# Balance_V0_1.net
KiCad netlist of a schematic drawn in Altium Designer
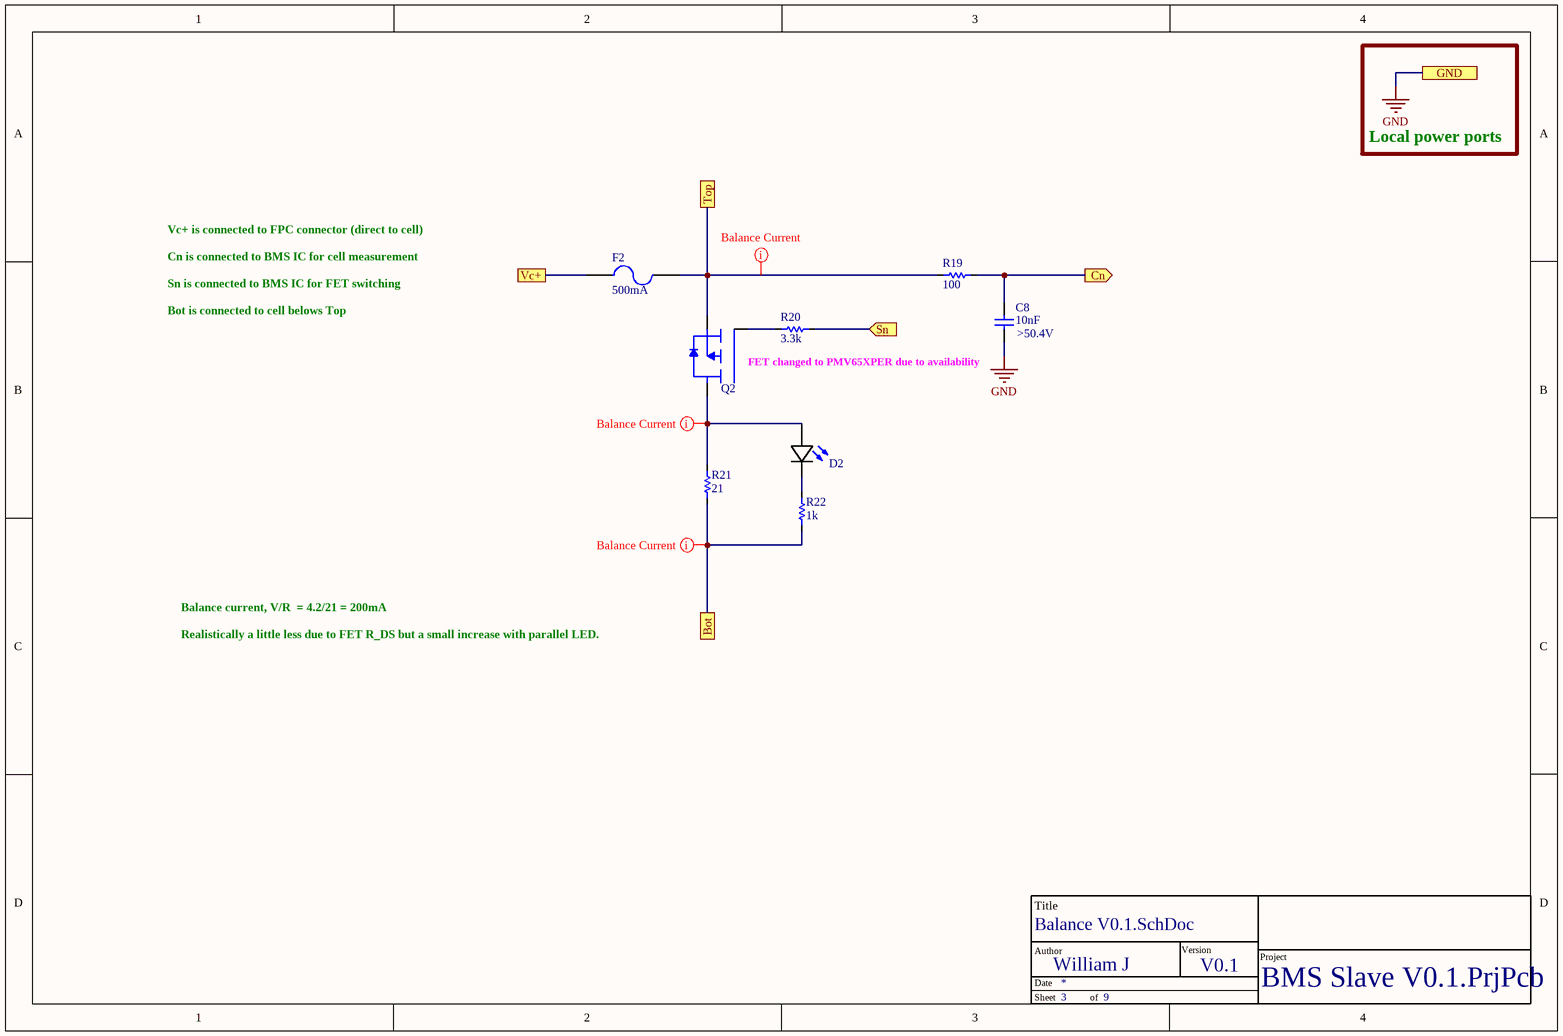
[diagram p0: Balance V0.1.SchDoc]

(export (version "E")
  (design (tool "Eeschema 10.0.6"))
  (components
    (comp (ref "*") (value "TitleBlock") (libsource (lib "SchematicLib") (part "TitleBlock")))
    (comp (ref "C8")
      (value "10nF")
      (footprint "C_0402")
      (description "Capacitor")
      (fields (field (name "VOLTAGE") ">50.4V") (field (name "Comment") "C1005X7S2A103K050BB"))
      (libsource (lib "Passives") (part "Capacitor"))
    )
    (comp (ref "D2")
      (value "150060BS55040")
      (footprint "LED (0603)")
      (description "LED BLUE DIFFUSED 0603 SMD")
      (fields (field (name "MANUFACTURER") "Wurth Electronics"))
      (libsource (lib "LEDLib") (part "150060BS55040"))
    )
    (comp (ref "F2")
      (value "0466.500NR")
      (footprint "0466.500NR")
      (fields
        (field (name "MANUFACTURER") "Littelfuse")
        (field (name "CURRENT RATING") "500mA")
        (field (name "PUBLISHER") "Altium Limited")
      )
      (libsource (lib "Miscellaneous Devices") (part "Fuse 2"))
    )
    (comp (ref "Q2")
      (value "NX2301PVL")
      (footprint "SOT95P230X110-3N")
      (description "MOSFET 20V P-Channel 2A")
      (libsource (lib "SchematicLib") (part "NX2301PVL"))
    )
    (comp (ref "R19")
      (value "100")
      (footprint "R_0402")
      (description "Resistor")
      (fields (field (name "Comment") "RC0402FR-07100RL"))
      (libsource (lib "Passives") (part "Resistor"))
    )
    (comp (ref "R20")
      (value "3.3k")
      (footprint "R_0402")
      (description "Resistor")
      (fields (field (name "Comment") "AC0402FR-073K3L"))
      (libsource (lib "Passives") (part "Resistor"))
    )
    (comp (ref "R21")
      (value "21")
      (footprint "R_2512")
      (description "Resistor")
      (fields (field (name "Comment") "CRM2512-JW-220ELF"))
      (libsource (lib "Passives") (part "Resistor"))
    )
    (comp (ref "R22")
      (value "1k")
      (footprint "R_0402")
      (description "Resistor")
      (fields (field (name "Comment") "RC0402FR-071KL"))
      (libsource (lib "Passives") (part "Resistor"))
    )
  )
  (nets
    (net (code "1") (name "/Bot") (class "Default")
      (node (ref "R21") (pin "1") (pinfunction "1_1") (pintype "passive"))
      (node (ref "R22") (pin "1") (pinfunction "1_1") (pintype "passive"))
    )
    (net (code "2") (name "/Cn") (class "Default")
      (node (ref "C8") (pin "2") (pinfunction "2_2") (pintype "passive"))
      (node (ref "R19") (pin "2") (pinfunction "2_2") (pintype "passive"))
    )
    (net (code "3") (name "/Sn") (class "Default")
      (node (ref "R20") (pin "2") (pinfunction "2_2") (pintype "passive"))
    )
    (net (code "4") (name "/Top") (class "Default")
      (node (ref "F2") (pin "2") (pinfunction "2_2") (pintype "passive"))
      (node (ref "Q2") (pin "2") (pinfunction "Source_2") (pintype "passive"))
      (node (ref "R19") (pin "1") (pinfunction "1_1") (pintype "passive"))
    )
    (net (code "5") (name "/Vc+") (class "Default")
      (node (ref "F2") (pin "1") (pinfunction "1_1") (pintype "passive"))
    )
    (net (code "6") (name "GND") (class "Default")
      (node (ref "C8") (pin "1") (pinfunction "1_1") (pintype "passive"))
    )
    (net (code "7") (name "Net-(D2-A)") (class "Default")
      (node (ref "D2") (pin "2") (pinfunction "A_2") (pintype "passive"))
      (node (ref "Q2") (pin "3") (pinfunction "Drain_3") (pintype "passive"))
      (node (ref "R21") (pin "2") (pinfunction "2_2") (pintype "passive"))
    )
    (net (code "8") (name "Net-(D2-K)") (class "Default")
      (node (ref "D2") (pin "1") (pinfunction "K_1") (pintype "passive"))
      (node (ref "R22") (pin "2") (pinfunction "2_2") (pintype "passive"))
    )
    (net (code "9") (name "Net-(Q2-Base)") (class "Default")
      (node (ref "Q2") (pin "1") (pinfunction "Base_1") (pintype "passive"))
      (node (ref "R20") (pin "1") (pinfunction "1_1") (pintype "passive"))
    )
  )
)
